# Hand-Exoskeleton-for-Climbing.net
KiCad netlist of a schematic drawn in EasyEDA Pro
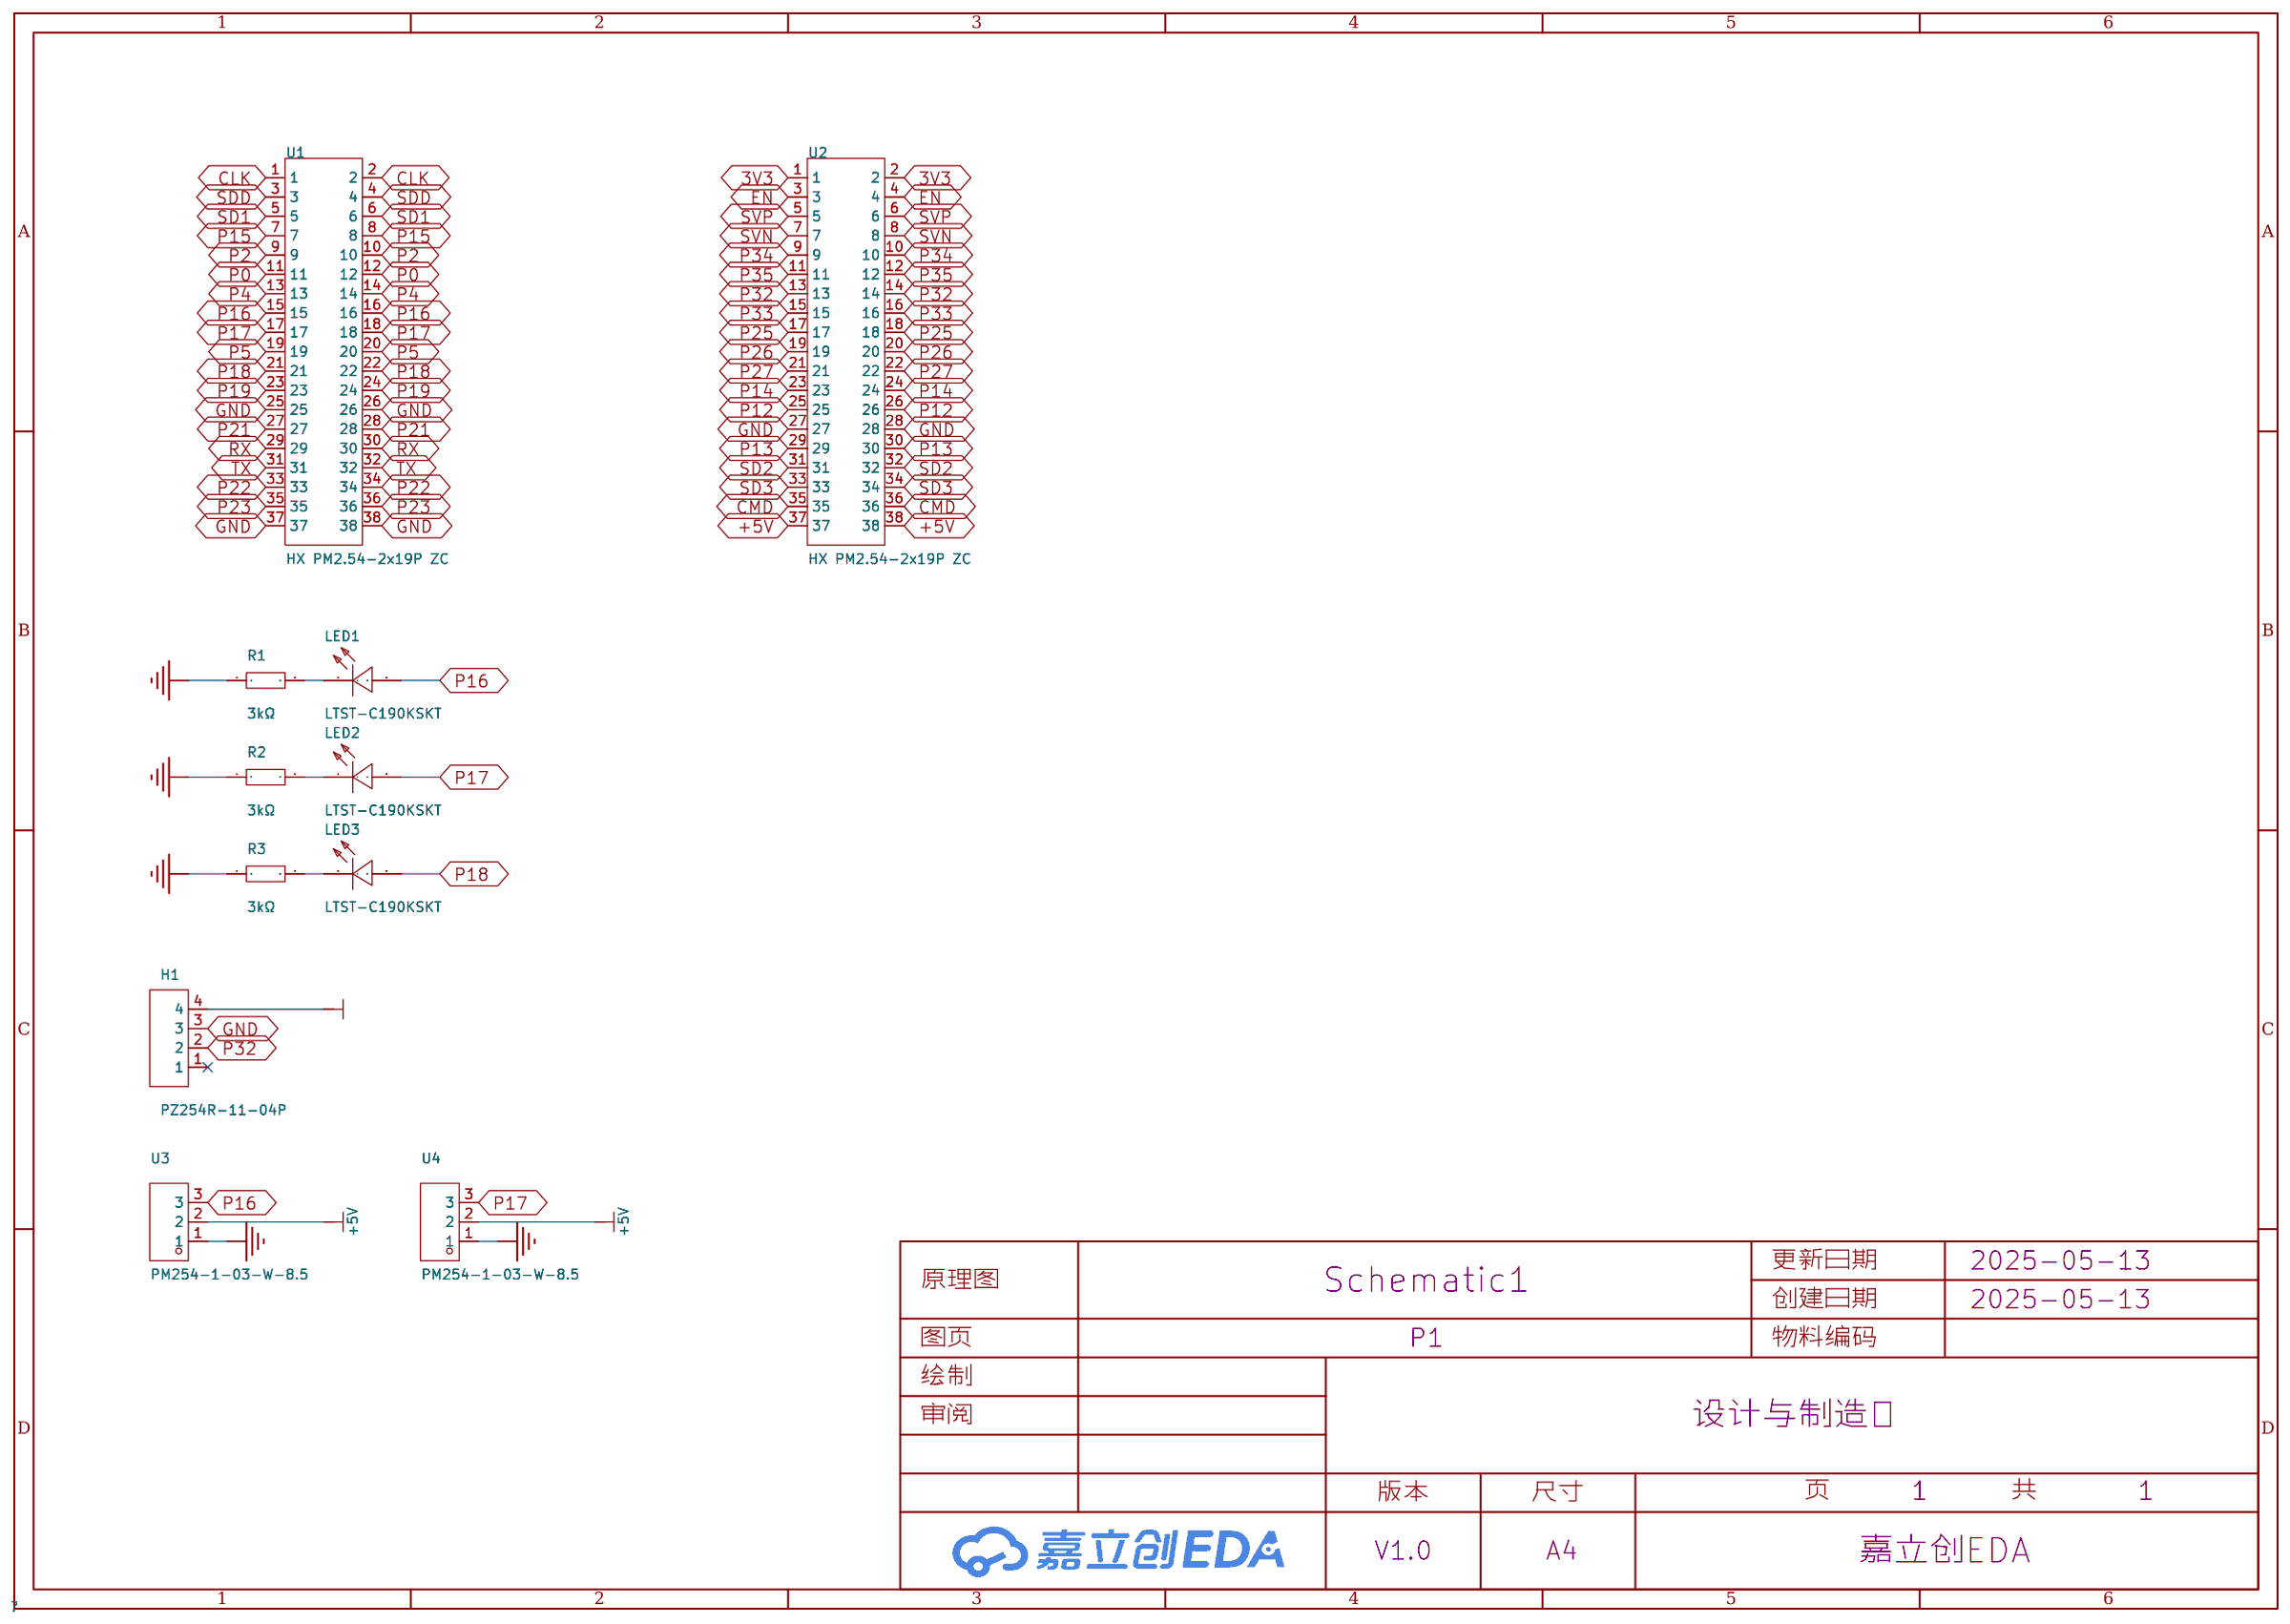
[diagram p0: schematic sheet]

(export (version "E")
  (design (tool "Eeschema 10.0.6"))
  (components
    (comp (ref "H1")
      (value "PZ254R-11-04P")
      (footprint "easyedapro:HDR-TH_4P-P2.54-H-M-W10.4")
      (fields (field (name "Manufacturer") "XFCN(兴飞)"))
      (libsource (lib "easyedapro") (part "PZ254R-11-04P"))
    )
    (comp (ref "LED1")
      (value "LTST-C190KSKT")
      (footprint "easyedapro:LED0603-RD")
      (fields (field (name "Manufacturer") "LITEON(光宝)"))
      (libsource (lib "easyedapro") (part "LTST-C190KSKT"))
    )
    (comp (ref "LED2")
      (value "LTST-C190KSKT")
      (footprint "easyedapro:LED0603-RD")
      (fields (field (name "Manufacturer") "LITEON(光宝)"))
      (libsource (lib "easyedapro") (part "LTST-C190KSKT"))
    )
    (comp (ref "LED3")
      (value "LTST-C190KSKT")
      (footprint "easyedapro:LED0603-RD")
      (fields (field (name "Manufacturer") "LITEON(光宝)"))
      (libsource (lib "easyedapro") (part "LTST-C190KSKT"))
    )
    (comp (ref "R1")
      (value "3kΩ")
      (footprint "easyedapro:R0603")
      (description "电阻类型:厚膜电阻;阻值:3kΩ;精度:±1%;功率:100mW;工作电压:75V;温度系数:±100ppm/°C;")
      (fields
        (field (name "Manufacturer Part") "0603WAF3001T5E")
        (field (name "Manufacturer") "UNI-ROYAL(厚声)")
      )
      (libsource (lib "easyedapro") (part "0603WAF3001T5E"))
    )
    (comp (ref "R2")
      (value "3kΩ")
      (footprint "easyedapro:R0603")
      (description "电阻类型:厚膜电阻;阻值:3kΩ;精度:±1%;功率:100mW;工作电压:75V;温度系数:±100ppm/°C;")
      (fields
        (field (name "Manufacturer Part") "0603WAF3001T5E")
        (field (name "Manufacturer") "UNI-ROYAL(厚声)")
      )
      (libsource (lib "easyedapro") (part "0603WAF3001T5E"))
    )
    (comp (ref "R3")
      (value "3kΩ")
      (footprint "easyedapro:R0603")
      (description "电阻类型:厚膜电阻;阻值:3kΩ;精度:±1%;功率:100mW;工作电压:75V;温度系数:±100ppm/°C;")
      (fields
        (field (name "Manufacturer Part") "0603WAF3001T5E")
        (field (name "Manufacturer") "UNI-ROYAL(厚声)")
      )
      (libsource (lib "easyedapro") (part "0603WAF3001T5E"))
    )
    (comp (ref "U1")
      (value "HX PM2.54-2x19P ZC")
      (footprint "easyedapro:HDR-TH_38P-P2.54-V-F-R2-C19-S2.54-1")
      (fields (field (name "Manufacturer") "hanxia(韩下)"))
      (libsource (lib "easyedapro") (part "HX PM2.54-2X19P ZC"))
    )
    (comp (ref "U2")
      (value "HX PM2.54-2x19P ZC")
      (footprint "easyedapro:HDR-TH_38P-P2.54-V-F-R2-C19-S2.54-1")
      (fields (field (name "Manufacturer") "hanxia(韩下)"))
      (libsource (lib "easyedapro") (part "HX PM2.54-2X19P ZC"))
    )
    (comp (ref "U3")
      (value "PM254-1-03-W-8.5")
      (footprint "easyedapro:HDR-TH_3P-P2.54-H-F-W10.0-N")
      (fields (field (name "Manufacturer") "HCTL(华灿天禄)"))
      (libsource (lib "easyedapro") (part "PM254-1-03-W-8.5"))
    )
    (comp (ref "U4")
      (value "PM254-1-03-W-8.5")
      (footprint "easyedapro:HDR-TH_3P-P2.54-H-F-W10.0-N")
      (fields (field (name "Manufacturer") "HCTL(华灿天禄)"))
      (libsource (lib "easyedapro") (part "PM254-1-03-W-8.5"))
    )
  )
  (nets
    (net (code "1") (name "+5V") (class "Default")
      (node (ref "U2") (pin "37") (pinfunction "37_37") (pintype "unspecified"))
      (node (ref "U2") (pin "38") (pinfunction "38_38") (pintype "unspecified"))
      (node (ref "U3") (pin "2") (pinfunction "2_2") (pintype "unspecified"))
      (node (ref "U4") (pin "2") (pinfunction "2_2") (pintype "unspecified"))
    )
    (net (code "2") (name "3V3") (class "Default")
      (node (ref "H1") (pin "4") (pinfunction "4_4") (pintype "unspecified"))
      (node (ref "U2") (pin "1") (pinfunction "1_1") (pintype "unspecified"))
      (node (ref "U2") (pin "2") (pinfunction "2_2") (pintype "unspecified"))
    )
    (net (code "3") (name "CLK") (class "Default")
      (node (ref "U1") (pin "1") (pinfunction "1_1") (pintype "unspecified"))
      (node (ref "U1") (pin "2") (pinfunction "2_2") (pintype "unspecified"))
    )
    (net (code "4") (name "CMD") (class "Default")
      (node (ref "U2") (pin "35") (pinfunction "35_35") (pintype "unspecified"))
      (node (ref "U2") (pin "36") (pinfunction "36_36") (pintype "unspecified"))
    )
    (net (code "5") (name "EN") (class "Default")
      (node (ref "U2") (pin "3") (pinfunction "3_3") (pintype "unspecified"))
      (node (ref "U2") (pin "4") (pinfunction "4_4") (pintype "unspecified"))
    )
    (net (code "6") (name "GND") (class "Default")
      (node (ref "H1") (pin "3") (pinfunction "3_3") (pintype "unspecified"))
      (node (ref "R1") (pin "1") (pinfunction "1_1") (pintype "input"))
      (node (ref "R2") (pin "1") (pinfunction "1_1") (pintype "input"))
      (node (ref "R3") (pin "1") (pinfunction "1_1") (pintype "input"))
      (node (ref "U1") (pin "25") (pinfunction "25_25") (pintype "unspecified"))
      (node (ref "U1") (pin "26") (pinfunction "26_26") (pintype "unspecified"))
      (node (ref "U1") (pin "37") (pinfunction "37_37") (pintype "unspecified"))
      (node (ref "U1") (pin "38") (pinfunction "38_38") (pintype "unspecified"))
      (node (ref "U2") (pin "27") (pinfunction "27_27") (pintype "unspecified"))
      (node (ref "U2") (pin "28") (pinfunction "28_28") (pintype "unspecified"))
      (node (ref "U3") (pin "1") (pinfunction "1_1") (pintype "unspecified"))
      (node (ref "U4") (pin "1") (pinfunction "1_1") (pintype "unspecified"))
    )
    (net (code "7") (name "Net-(LED1--)") (class "Default")
      (node (ref "LED1") (pin "1") (pinfunction "-_1") (pintype "unspecified"))
      (node (ref "R1") (pin "2") (pinfunction "2_2") (pintype "input"))
    )
    (net (code "8") (name "Net-(LED2--)") (class "Default")
      (node (ref "LED2") (pin "1") (pinfunction "-_1") (pintype "unspecified"))
      (node (ref "R2") (pin "2") (pinfunction "2_2") (pintype "input"))
    )
    (net (code "9") (name "Net-(LED3--)") (class "Default")
      (node (ref "LED3") (pin "1") (pinfunction "-_1") (pintype "unspecified"))
      (node (ref "R3") (pin "2") (pinfunction "2_2") (pintype "input"))
    )
    (net (code "10") (name "P0") (class "Default")
      (node (ref "U1") (pin "11") (pinfunction "11_11") (pintype "unspecified"))
      (node (ref "U1") (pin "12") (pinfunction "12_12") (pintype "unspecified"))
    )
    (net (code "11") (name "P2") (class "Default")
      (node (ref "U1") (pin "10") (pinfunction "10_10") (pintype "unspecified"))
      (node (ref "U1") (pin "9") (pinfunction "9_9") (pintype "unspecified"))
    )
    (net (code "12") (name "P4") (class "Default")
      (node (ref "U1") (pin "13") (pinfunction "13_13") (pintype "unspecified"))
      (node (ref "U1") (pin "14") (pinfunction "14_14") (pintype "unspecified"))
    )
    (net (code "13") (name "P5") (class "Default")
      (node (ref "U1") (pin "19") (pinfunction "19_19") (pintype "unspecified"))
      (node (ref "U1") (pin "20") (pinfunction "20_20") (pintype "unspecified"))
    )
    (net (code "14") (name "P12") (class "Default")
      (node (ref "U2") (pin "25") (pinfunction "25_25") (pintype "unspecified"))
      (node (ref "U2") (pin "26") (pinfunction "26_26") (pintype "unspecified"))
    )
    (net (code "15") (name "P13") (class "Default")
      (node (ref "U2") (pin "29") (pinfunction "29_29") (pintype "unspecified"))
      (node (ref "U2") (pin "30") (pinfunction "30_30") (pintype "unspecified"))
    )
    (net (code "16") (name "P14") (class "Default")
      (node (ref "U2") (pin "23") (pinfunction "23_23") (pintype "unspecified"))
      (node (ref "U2") (pin "24") (pinfunction "24_24") (pintype "unspecified"))
    )
    (net (code "17") (name "P15") (class "Default")
      (node (ref "U1") (pin "7") (pinfunction "7_7") (pintype "unspecified"))
      (node (ref "U1") (pin "8") (pinfunction "8_8") (pintype "unspecified"))
    )
    (net (code "18") (name "P16") (class "Default")
      (node (ref "LED1") (pin "2") (pinfunction "+_2") (pintype "unspecified"))
      (node (ref "U1") (pin "15") (pinfunction "15_15") (pintype "unspecified"))
      (node (ref "U1") (pin "16") (pinfunction "16_16") (pintype "unspecified"))
      (node (ref "U3") (pin "3") (pinfunction "3_3") (pintype "unspecified"))
    )
    (net (code "19") (name "P17") (class "Default")
      (node (ref "LED2") (pin "2") (pinfunction "+_2") (pintype "unspecified"))
      (node (ref "U1") (pin "17") (pinfunction "17_17") (pintype "unspecified"))
      (node (ref "U1") (pin "18") (pinfunction "18_18") (pintype "unspecified"))
      (node (ref "U4") (pin "3") (pinfunction "3_3") (pintype "unspecified"))
    )
    (net (code "20") (name "P18") (class "Default")
      (node (ref "LED3") (pin "2") (pinfunction "+_2") (pintype "unspecified"))
      (node (ref "U1") (pin "21") (pinfunction "21_21") (pintype "unspecified"))
      (node (ref "U1") (pin "22") (pinfunction "22_22") (pintype "unspecified"))
    )
    (net (code "21") (name "P19") (class "Default")
      (node (ref "U1") (pin "23") (pinfunction "23_23") (pintype "unspecified"))
      (node (ref "U1") (pin "24") (pinfunction "24_24") (pintype "unspecified"))
    )
    (net (code "22") (name "P21") (class "Default")
      (node (ref "U1") (pin "27") (pinfunction "27_27") (pintype "unspecified"))
      (node (ref "U1") (pin "28") (pinfunction "28_28") (pintype "unspecified"))
    )
    (net (code "23") (name "P22") (class "Default")
      (node (ref "U1") (pin "33") (pinfunction "33_33") (pintype "unspecified"))
      (node (ref "U1") (pin "34") (pinfunction "34_34") (pintype "unspecified"))
    )
    (net (code "24") (name "P23") (class "Default")
      (node (ref "U1") (pin "35") (pinfunction "35_35") (pintype "unspecified"))
      (node (ref "U1") (pin "36") (pinfunction "36_36") (pintype "unspecified"))
    )
    (net (code "25") (name "P25") (class "Default")
      (node (ref "U2") (pin "17") (pinfunction "17_17") (pintype "unspecified"))
      (node (ref "U2") (pin "18") (pinfunction "18_18") (pintype "unspecified"))
    )
    (net (code "26") (name "P26") (class "Default")
      (node (ref "U2") (pin "19") (pinfunction "19_19") (pintype "unspecified"))
      (node (ref "U2") (pin "20") (pinfunction "20_20") (pintype "unspecified"))
    )
    (net (code "27") (name "P27") (class "Default")
      (node (ref "U2") (pin "21") (pinfunction "21_21") (pintype "unspecified"))
      (node (ref "U2") (pin "22") (pinfunction "22_22") (pintype "unspecified"))
    )
    (net (code "28") (name "P32") (class "Default")
      (node (ref "H1") (pin "2") (pinfunction "2_2") (pintype "unspecified"))
      (node (ref "U2") (pin "13") (pinfunction "13_13") (pintype "unspecified"))
      (node (ref "U2") (pin "14") (pinfunction "14_14") (pintype "unspecified"))
    )
    (net (code "29") (name "P33") (class "Default")
      (node (ref "U2") (pin "15") (pinfunction "15_15") (pintype "unspecified"))
      (node (ref "U2") (pin "16") (pinfunction "16_16") (pintype "unspecified"))
    )
    (net (code "30") (name "P34") (class "Default")
      (node (ref "U2") (pin "10") (pinfunction "10_10") (pintype "unspecified"))
      (node (ref "U2") (pin "9") (pinfunction "9_9") (pintype "unspecified"))
    )
    (net (code "31") (name "P35") (class "Default")
      (node (ref "U2") (pin "11") (pinfunction "11_11") (pintype "unspecified"))
      (node (ref "U2") (pin "12") (pinfunction "12_12") (pintype "unspecified"))
    )
    (net (code "32") (name "RX") (class "Default")
      (node (ref "U1") (pin "29") (pinfunction "29_29") (pintype "unspecified"))
      (node (ref "U1") (pin "30") (pinfunction "30_30") (pintype "unspecified"))
    )
    (net (code "33") (name "SD1") (class "Default")
      (node (ref "U1") (pin "5") (pinfunction "5_5") (pintype "unspecified"))
      (node (ref "U1") (pin "6") (pinfunction "6_6") (pintype "unspecified"))
    )
    (net (code "34") (name "SD2") (class "Default")
      (node (ref "U2") (pin "31") (pinfunction "31_31") (pintype "unspecified"))
      (node (ref "U2") (pin "32") (pinfunction "32_32") (pintype "unspecified"))
    )
    (net (code "35") (name "SD3") (class "Default")
      (node (ref "U2") (pin "33") (pinfunction "33_33") (pintype "unspecified"))
      (node (ref "U2") (pin "34") (pinfunction "34_34") (pintype "unspecified"))
    )
    (net (code "36") (name "SDD") (class "Default")
      (node (ref "U1") (pin "3") (pinfunction "3_3") (pintype "unspecified"))
      (node (ref "U1") (pin "4") (pinfunction "4_4") (pintype "unspecified"))
    )
    (net (code "37") (name "SVN") (class "Default")
      (node (ref "U2") (pin "7") (pinfunction "7_7") (pintype "unspecified"))
      (node (ref "U2") (pin "8") (pinfunction "8_8") (pintype "unspecified"))
    )
    (net (code "38") (name "SVP") (class "Default")
      (node (ref "U2") (pin "5") (pinfunction "5_5") (pintype "unspecified"))
      (node (ref "U2") (pin "6") (pinfunction "6_6") (pintype "unspecified"))
    )
    (net (code "39") (name "TX") (class "Default")
      (node (ref "U1") (pin "31") (pinfunction "31_31") (pintype "unspecified"))
      (node (ref "U1") (pin "32") (pinfunction "32_32") (pintype "unspecified"))
    )
    (net (code "40") (name "unconnected-(H1-Pad1)") (class "Default")
      (node (ref "H1") (pin "1") (pinfunction "1_1") (pintype "unspecified+no_connect"))
    )
  )
)
